# LED_Board_--_Single.net
KiCad netlist of a schematic drawn in EAGLE
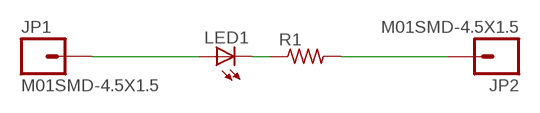
[diagram p0: schematic, sheet 1]

(export (version "E")
  (design (tool "Eeschema 10.0.6"))
  (components
    (comp (ref "JP1")
      (value "M01SMD-4.5X1.5")
      (footprint "eagle-import:PAD-1.5X4.5")
      (libsource (lib "eagle-import") (part "M01SMD-4.5X1.5"))
    )
    (comp (ref "JP2")
      (value "M01SMD-4.5X1.5")
      (footprint "eagle-import:PAD-1.5X4.5")
      (libsource (lib "eagle-import") (part "M01SMD-4.5X1.5"))
    )
    (comp (ref "LED1")
      (value "LEDSML0603")
      (footprint "eagle-import:SML0603")
      (libsource (lib "eagle-import") (part "LEDSML0603"))
    )
    (comp (ref "R1")
      (value "R-US_M0805")
      (footprint "eagle-import:M0805")
      (libsource (lib "eagle-import") (part "R-US_M0805"))
    )
  )
  (nets
    (net (code "1") (name "Net-(JP1-1)") (class "Default")
      (node (ref "JP1") (pin "P$1") (pinfunction "1_P$1") (pintype "passive"))
      (node (ref "LED1") (pin "A") (pinfunction "A_A") (pintype "passive"))
    )
    (net (code "2") (name "Net-(JP2-1)") (class "Default")
      (node (ref "JP2") (pin "P$1") (pinfunction "1_P$1") (pintype "passive"))
      (node (ref "R1") (pin "2") (pinfunction "2_2") (pintype "passive"))
    )
    (net (code "3") (name "Net-(LED1-PadC)") (class "Default")
      (node (ref "LED1") (pin "C") (pinfunction "C_C") (pintype "passive"))
      (node (ref "R1") (pin "1") (pinfunction "1_1") (pintype "passive"))
    )
  )
)
